# board.net
KiCad netlist of a schematic drawn in EAGLE
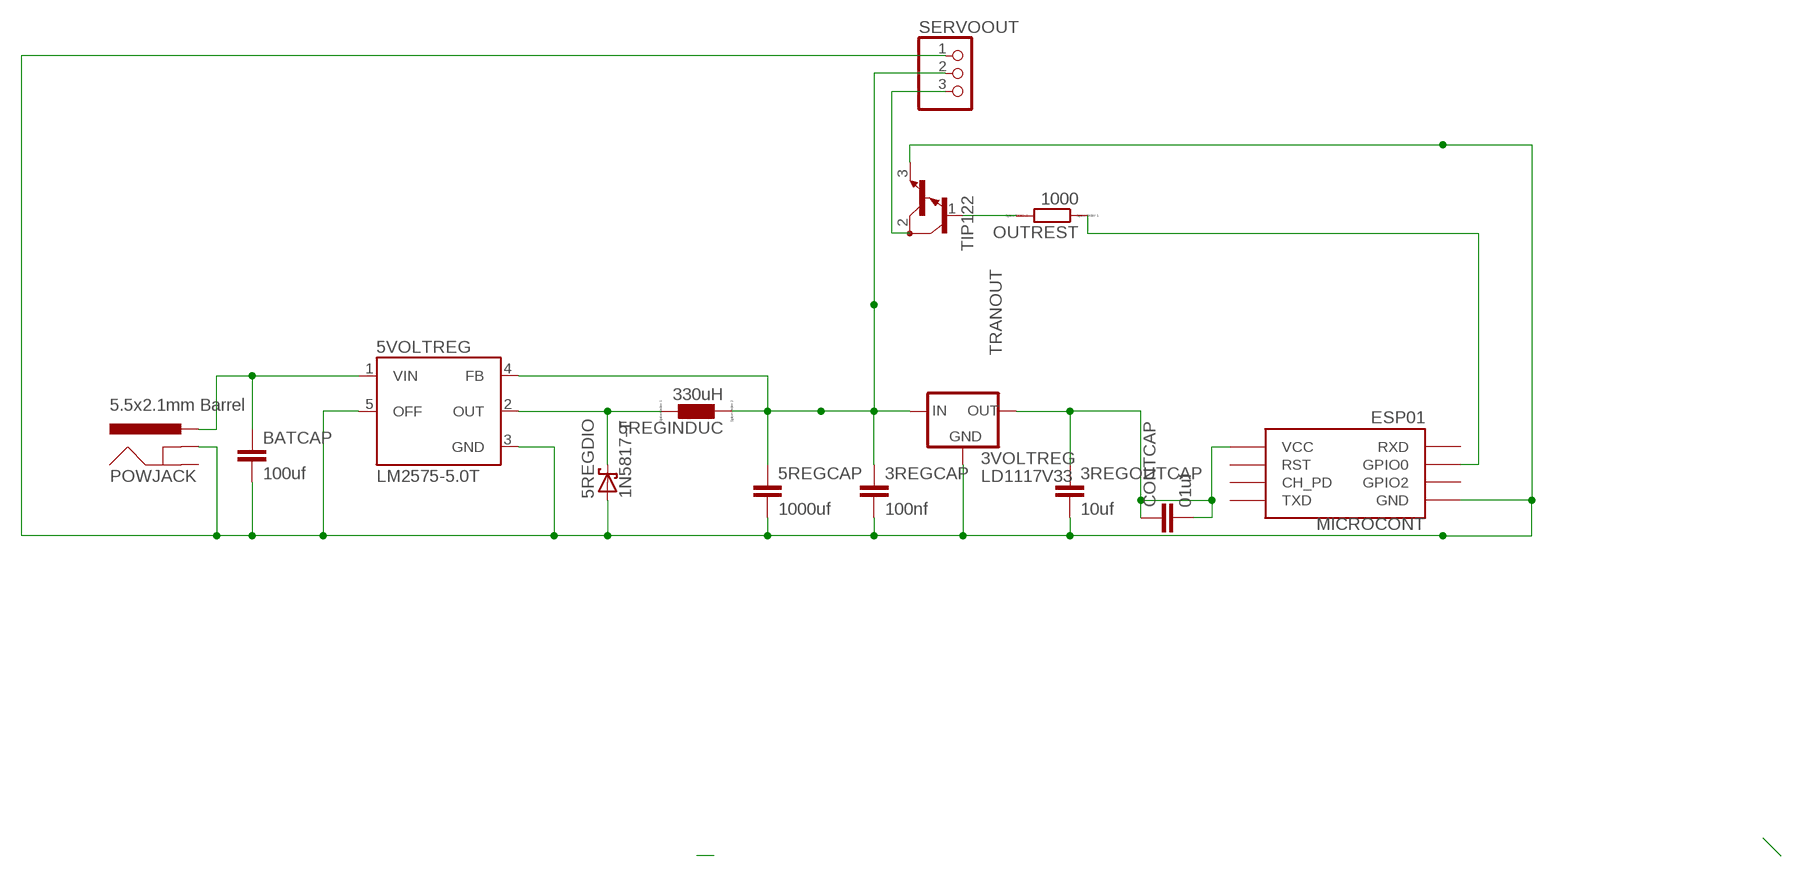
[diagram p0: schematic, sheet 1]

(export (version "E")
  (design (tool "Eeschema 10.0.6"))
  (components
    (comp (ref "3REGCAP")
      (value "100nf")
      (footprint "eagle-import:C5B2.5")
      (libsource (lib "eagle-import") (part "C5/2.5"))
    )
    (comp (ref "3REGOUTCAP")
      (value "10uf")
      (footprint "eagle-import:C5B2.5")
      (libsource (lib "eagle-import") (part "C5/2.5"))
    )
    (comp (ref "3VOLTREG")
      (value "LD1117V33")
      (footprint "eagle-import:LD1117V33")
      (libsource (lib "eagle-import") (part "LD1117V33"))
    )
    (comp (ref "5REGCAP")
      (value "1000uf")
      (footprint "eagle-import:C5B2.5")
      (libsource (lib "eagle-import") (part "C5/2.5"))
    )
    (comp (ref "5REGDIO")
      (value "1N5817-T")
      (footprint "eagle-import:DO41-7.6")
      (libsource (lib "eagle-import") (part "1N5817-T"))
    )
    (comp (ref "5REGINDUC")
      (value "330uH")
      (footprint "eagle-import:0204_7")
      (libsource (lib "eagle-import") (part "L0204/7"))
    )
    (comp (ref "5VOLTREG")
      (value "LM2575-5.0T")
      (footprint "eagle-import:TO220-5")
      (libsource (lib "eagle-import") (part "LM2575-5.0T"))
    )
    (comp (ref "BATCAP")
      (value "100uf")
      (footprint "eagle-import:C5B2.5")
      (libsource (lib "eagle-import") (part "C5/2.5"))
    )
    (comp (ref "CONTCAP")
      (value "01uf")
      (footprint "eagle-import:C5B2.5")
      (libsource (lib "eagle-import") (part "C5/2.5"))
    )
    (comp (ref "MICROCONT")
      (value "ESP01")
      (footprint "eagle-import:ESP01")
      (libsource (lib "eagle-import") (part "ESP01"))
    )
    (comp (ref "OUTREST")
      (value "1000")
      (footprint "eagle-import:0207_10")
      (libsource (lib "eagle-import") (part "R0207/10"))
    )
    (comp (ref "POWJACK")
      (value "5.5x2.1mm Barrel")
      (footprint "eagle-import:POWER_JACK_SMD")
      (libsource (lib "eagle-import") (part "POWER_JACKSMD"))
    )
    (comp (ref "SERVOOUT")
      (value "PINHD-1X3")
      (footprint "eagle-import:1X03")
      (libsource (lib "eagle-import") (part "PINHD-1X3"))
    )
    (comp (ref "TRANOUT")
      (value "TIP122")
      (footprint "eagle-import:TO220")
      (libsource (lib "eagle-import") (part "TIP122"))
    )
  )
  (nets
    (net (code "1") (name "Net-(3REGOUTCAP-Pad1)") (class "Default")
      (node (ref "3REGOUTCAP") (pin "1") (pinfunction "1_1") (pintype "passive"))
      (node (ref "3VOLTREG") (pin "OUT") (pinfunction "OUT_OUT") (pintype "output"))
      (node (ref "CONTCAP") (pin "1") (pinfunction "1_1") (pintype "passive"))
      (node (ref "CONTCAP") (pin "2") (pinfunction "2_2") (pintype "passive"))
      (node (ref "MICROCONT") (pin "VCC") (pinfunction "VCC_VCC") (pintype "bidirectional"))
    )
    (net (code "2") (name "Net-(5VOLTREG-FB)") (class "Default")
      (node (ref "3REGCAP") (pin "1") (pinfunction "1_1") (pintype "passive"))
      (node (ref "3VOLTREG") (pin "IN") (pinfunction "IN_IN") (pintype "input"))
      (node (ref "5REGCAP") (pin "1") (pinfunction "1_1") (pintype "passive"))
      (node (ref "5REGINDUC") (pin "2") (pinfunction "2_2") (pintype "passive"))
      (node (ref "5VOLTREG") (pin "4") (pinfunction "FB_4") (pintype "input"))
      (node (ref "SERVOOUT") (pin "2") (pinfunction "2_2") (pintype "passive"))
    )
    (net (code "3") (name "Net-(5VOLTREG-GND)") (class "Default")
      (node (ref "3REGCAP") (pin "2") (pinfunction "2_2") (pintype "passive"))
      (node (ref "3REGOUTCAP") (pin "2") (pinfunction "2_2") (pintype "passive"))
      (node (ref "3VOLTREG") (pin "GND") (pinfunction "GND_GND") (pintype "input"))
      (node (ref "5REGCAP") (pin "2") (pinfunction "2_2") (pintype "passive"))
      (node (ref "5REGDIO") (pin "A") (pinfunction "A_A") (pintype "passive"))
      (node (ref "5VOLTREG") (pin "3") (pinfunction "GND_3") (pintype "power_in"))
      (node (ref "5VOLTREG") (pin "5") (pinfunction "OFF_5") (pintype "input"))
      (node (ref "BATCAP") (pin "2") (pinfunction "2_2") (pintype "passive"))
      (node (ref "MICROCONT") (pin "GND") (pinfunction "GND_GND") (pintype "bidirectional"))
      (node (ref "POWJACK") (pin "GND") (pinfunction "GNDBREAK_GND") (pintype "bidirectional"))
      (node (ref "SERVOOUT") (pin "1") (pinfunction "1_1") (pintype "passive"))
      (node (ref "TRANOUT") (pin "3") (pinfunction "E_3") (pintype "passive"))
    )
    (net (code "4") (name "Net-(5VOLTREG-OUT)") (class "Default")
      (node (ref "5REGDIO") (pin "C") (pinfunction "C_C") (pintype "passive"))
      (node (ref "5REGINDUC") (pin "1") (pinfunction "1_1") (pintype "passive"))
      (node (ref "5VOLTREG") (pin "2") (pinfunction "OUT_2") (pintype "output"))
    )
    (net (code "5") (name "Net-(5VOLTREG-VIN)") (class "Default")
      (node (ref "5VOLTREG") (pin "1") (pinfunction "VIN_1") (pintype "power_in"))
      (node (ref "BATCAP") (pin "1") (pinfunction "1_1") (pintype "passive"))
      (node (ref "POWJACK") (pin "VIN0") (pinfunction "PWR_VIN0") (pintype "bidirectional"))
    )
    (net (code "6") (name "Net-(MICROCONT-PadGPIO0)") (class "Default")
      (node (ref "MICROCONT") (pin "GPIO0") (pinfunction "GPIO0_GPIO0") (pintype "bidirectional"))
      (node (ref "OUTREST") (pin "1") (pinfunction "1_1") (pintype "passive"))
    )
    (net (code "7") (name "Net-(TRANOUT-B)") (class "Default")
      (node (ref "OUTREST") (pin "2") (pinfunction "2_2") (pintype "passive"))
      (node (ref "TRANOUT") (pin "1") (pinfunction "B_1") (pintype "passive"))
    )
    (net (code "8") (name "Net-(TRANOUT-C)") (class "Default")
      (node (ref "SERVOOUT") (pin "3") (pinfunction "3_3") (pintype "passive"))
      (node (ref "TRANOUT") (pin "2") (pinfunction "C_2") (pintype "passive"))
    )
    (net (code "9") (name "unconnected-(MICROCONT-PadCH_PD)") (class "Default")
      (node (ref "MICROCONT") (pin "CH_PD") (pinfunction "CH_PD_CH_PD") (pintype "bidirectional"))
    )
    (net (code "10") (name "unconnected-(MICROCONT-PadGPIO2)") (class "Default")
      (node (ref "MICROCONT") (pin "GPIO2") (pinfunction "GPIO2_GPIO2") (pintype "bidirectional"))
    )
    (net (code "11") (name "unconnected-(MICROCONT-PadRST)") (class "Default")
      (node (ref "MICROCONT") (pin "RST") (pinfunction "RST_RST") (pintype "bidirectional"))
    )
    (net (code "12") (name "unconnected-(MICROCONT-RXD-PadRX)") (class "Default")
      (node (ref "MICROCONT") (pin "RX") (pinfunction "RXD_RX") (pintype "bidirectional"))
    )
    (net (code "13") (name "unconnected-(MICROCONT-TXD-PadTX)") (class "Default")
      (node (ref "MICROCONT") (pin "TX") (pinfunction "TXD_TX") (pintype "bidirectional"))
    )
    (net (code "14") (name "unconnected-(POWJACK-GND-PadP$4)") (class "Default")
      (node (ref "POWJACK") (pin "P$4") (pinfunction "GND_P$4") (pintype "bidirectional"))
    )
  )
)
